# ADC_channel.net
KiCad netlist of a schematic drawn in Altium Designer
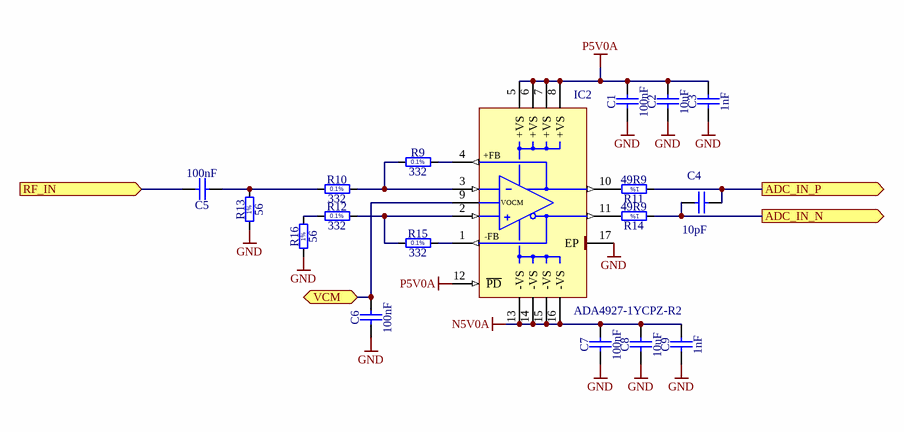
[diagram p0: ADC_channel.SchDoc]

(export (version "E")
  (design (tool "Eeschema 10.0.6"))
  (components
    (comp (ref "C1")
      (value "100nF")
      (footprint "CAPC1005X55N")
      (description "Non-polarised capacitor")
      (fields
        (field (name "PART NUMBER") "CC0402_100NF_16V_10%_X5R")
        (field (name "VOLTAGE") "16V")
        (field (name "AUTHOR") "CERN DEM JLC")
      )
      (libsource (lib "Capacitors") (part "Capacitor - non polarized"))
    )
    (comp (ref "C2")
      (value "10uF")
      (footprint "CAPC1608X87N")
      (description "Non-polarised capacitor")
      (fields
        (field (name "PART NUMBER") "CC0603_10UF_6.3V_20%_X5R")
        (field (name "VOLTAGE") "6.3V")
        (field (name "AUTHOR") "CERN DEM JLC")
      )
      (libsource (lib "Capacitors") (part "Capacitor - non polarized"))
    )
    (comp (ref "C3")
      (value "1nF")
      (footprint "CAPC1005X55N")
      (description "Non-polarised capacitor")
      (fields
        (field (name "PART NUMBER") "CC0402_1NF_50V_10%_X7R")
        (field (name "VOLTAGE") "50V")
        (field (name "AUTHOR") "CERN DEM JLC")
      )
      (libsource (lib "Capacitors") (part "Capacitor - non polarized"))
    )
    (comp (ref "C4")
      (value "10pF")
      (footprint "CAPC1608X87N")
      (description "Non-polarised capacitor")
      (fields
        (field (name "PART NUMBER") "CC0603_10PF_50V_5%_NP0")
        (field (name "VOLTAGE") "50V")
        (field (name "AUTHOR") "CERN DEM JLC")
      )
      (libsource (lib "Capacitors") (part "Capacitor - non polarized"))
    )
    (comp (ref "C5")
      (value "100nF")
      (footprint "CAPC1005X55N")
      (description "Non-polarised capacitor")
      (fields
        (field (name "PART NUMBER") "CC0402_100NF_16V_10%_X5R")
        (field (name "VOLTAGE") "16V")
        (field (name "AUTHOR") "CERN DEM JLC")
      )
      (libsource (lib "Capacitors") (part "Capacitor - non polarized"))
    )
    (comp (ref "C6")
      (value "100nF")
      (footprint "CAPC1005X55N")
      (description "Non-polarised capacitor")
      (fields
        (field (name "PART NUMBER") "CC0402_100NF_16V_10%_X5R")
        (field (name "VOLTAGE") "16V")
        (field (name "AUTHOR") "CERN DEM JLC")
      )
      (libsource (lib "Capacitors") (part "Capacitor - non polarized"))
    )
    (comp (ref "C7")
      (value "100nF")
      (footprint "CAPC1005X55N")
      (description "Non-polarised capacitor")
      (fields
        (field (name "PART NUMBER") "CC0402_100NF_16V_10%_X5R")
        (field (name "VOLTAGE") "16V")
        (field (name "AUTHOR") "CERN DEM JLC")
      )
      (libsource (lib "Capacitors") (part "Capacitor - non polarized"))
    )
    (comp (ref "C8")
      (value "10uF")
      (footprint "CAPC1608X87N")
      (description "Non-polarised capacitor")
      (fields
        (field (name "PART NUMBER") "CC0603_10UF_6.3V_20%_X5R")
        (field (name "VOLTAGE") "6.3V")
        (field (name "AUTHOR") "CERN DEM JLC")
      )
      (libsource (lib "Capacitors") (part "Capacitor - non polarized"))
    )
    (comp (ref "C9")
      (value "1nF")
      (footprint "CAPC1005X55N")
      (description "Non-polarised capacitor")
      (fields
        (field (name "PART NUMBER") "CC0402_1NF_50V_10%_X7R")
        (field (name "VOLTAGE") "50V")
        (field (name "AUTHOR") "CERN DEM JLC")
      )
      (libsource (lib "Capacitors") (part "Capacitor - non polarized"))
    )
    (comp (ref "IC2")
      (value "ADA4927-1YCPZ-R2")
      (footprint "QFN50P300X300X100-17N-S145")
      (description "Ultralow Distortion Current Feedback Differential ADC Driver")
      (fields (field (name "MANUFACTURER") "ANALOG DEVICES") (field (name "AUTHOR") "CERN DEM JLC"))
      (libsource (lib "ICs And Semiconductors") (part "ADA4927-1"))
    )
    (comp (ref "R9")
      (value "332")
      (footprint "RESC1608X55N")
      (description "Resistor - 0.1%")
      (fields
        (field (name "PART NUMBER") "R0603_332R_0.1%_0.063W_10PPM")
        (field (name "POWER") "0.063W")
        (field (name "AUTHOR") "CERN DEM JLC")
      )
      (libsource (lib "Resistors") (part "Resistor - 0.1%"))
    )
    (comp (ref "R10")
      (value "332")
      (footprint "RESC1608X55N")
      (description "Resistor - 0.1%")
      (fields
        (field (name "PART NUMBER") "R0603_332R_0.1%_0.063W_10PPM")
        (field (name "POWER") "0.063W")
        (field (name "AUTHOR") "CERN DEM JLC")
      )
      (libsource (lib "Resistors") (part "Resistor - 0.1%"))
    )
    (comp (ref "R11")
      (value "49R9")
      (footprint "RESC1005X40N")
      (description "Resistor - 1%")
      (fields
        (field (name "PART NUMBER") "R0402_49R9_1%_0.0625W_100PPM")
        (field (name "POWER") "0.0625W")
        (field (name "AUTHOR") "CERN DEM JLC")
      )
      (libsource (lib "Resistors") (part "Resistor - 1%"))
    )
    (comp (ref "R12")
      (value "332")
      (footprint "RESC1608X55N")
      (description "Resistor - 0.1%")
      (fields
        (field (name "PART NUMBER") "R0603_332R_0.1%_0.063W_10PPM")
        (field (name "POWER") "0.063W")
        (field (name "AUTHOR") "CERN DEM JLC")
      )
      (libsource (lib "Resistors") (part "Resistor - 0.1%"))
    )
    (comp (ref "R13")
      (value "56")
      (footprint "RESC1005X40N")
      (description "Resistor - 1%")
      (fields
        (field (name "PART NUMBER") "R0402_56R_1%_0.0625W_100PPM")
        (field (name "POWER") "0.0625W")
        (field (name "AUTHOR") "CERN DEM JLC")
      )
      (libsource (lib "Resistors") (part "Resistor - 1%"))
    )
    (comp (ref "R14")
      (value "49R9")
      (footprint "RESC1005X40N")
      (description "Resistor - 1%")
      (fields
        (field (name "PART NUMBER") "R0402_49R9_1%_0.0625W_100PPM")
        (field (name "POWER") "0.0625W")
        (field (name "AUTHOR") "CERN DEM JLC")
      )
      (libsource (lib "Resistors") (part "Resistor - 1%"))
    )
    (comp (ref "R15")
      (value "332")
      (footprint "RESC1608X55N")
      (description "Resistor - 0.1%")
      (fields
        (field (name "PART NUMBER") "R0603_332R_0.1%_0.063W_10PPM")
        (field (name "POWER") "0.063W")
        (field (name "AUTHOR") "CERN DEM JLC")
      )
      (libsource (lib "Resistors") (part "Resistor - 0.1%"))
    )
    (comp (ref "R16")
      (value "56")
      (footprint "RESC1005X40N")
      (description "Resistor - 1%")
      (fields
        (field (name "PART NUMBER") "R0402_56R_1%_0.0625W_100PPM")
        (field (name "POWER") "0.0625W")
        (field (name "AUTHOR") "CERN DEM JLC")
      )
      (libsource (lib "Resistors") (part "Resistor - 1%"))
    )
  )
  (nets
    (net (code "1") (name "/ADC_IN_N") (class "Default")
      (node (ref "C4") (pin "1") (pinfunction "1_1") (pintype "passive"))
      (node (ref "R14") (pin "1") (pinfunction "1_1") (pintype "passive"))
    )
    (net (code "2") (name "/ADC_IN_P") (class "Default")
      (node (ref "C4") (pin "2") (pinfunction "2_2") (pintype "passive"))
      (node (ref "R11") (pin "1") (pinfunction "1_1") (pintype "passive"))
    )
    (net (code "3") (name "/RF_IN") (class "Default")
      (node (ref "C5") (pin "2") (pinfunction "2_2") (pintype "passive"))
    )
    (net (code "4") (name "/VCM") (class "Default")
      (node (ref "C6") (pin "2") (pinfunction "2_2") (pintype "passive"))
      (node (ref "IC2") (pin "9") (pinfunction "VOCM_9") (pintype "passive"))
    )
    (net (code "5") (name "GND") (class "Default")
      (node (ref "C1") (pin "1") (pinfunction "1_1") (pintype "passive"))
      (node (ref "C2") (pin "1") (pinfunction "1_1") (pintype "passive"))
      (node (ref "C3") (pin "1") (pinfunction "1_1") (pintype "passive"))
      (node (ref "C6") (pin "1") (pinfunction "1_1") (pintype "passive"))
      (node (ref "C7") (pin "1") (pinfunction "1_1") (pintype "passive"))
      (node (ref "C8") (pin "1") (pinfunction "1_1") (pintype "passive"))
      (node (ref "C9") (pin "1") (pinfunction "1_1") (pintype "passive"))
      (node (ref "IC2") (pin "17") (pinfunction "EP_17") (pintype "power_in"))
      (node (ref "R13") (pin "1") (pinfunction "1_1") (pintype "passive"))
      (node (ref "R16") (pin "1") (pinfunction "1_1") (pintype "passive"))
    )
    (net (code "6") (name "N5V0A") (class "Default")
      (node (ref "C7") (pin "2") (pinfunction "2_2") (pintype "passive"))
      (node (ref "C8") (pin "2") (pinfunction "2_2") (pintype "passive"))
      (node (ref "C9") (pin "2") (pinfunction "2_2") (pintype "passive"))
      (node (ref "IC2") (pin "13") (pinfunction "-VS_13") (pintype "power_in"))
      (node (ref "IC2") (pin "14") (pinfunction "-VS_14") (pintype "power_in"))
      (node (ref "IC2") (pin "15") (pinfunction "-VS_15") (pintype "power_in"))
      (node (ref "IC2") (pin "16") (pinfunction "-VS_16") (pintype "power_in"))
    )
    (net (code "7") (name "Net-(C5-Pad1)") (class "Default")
      (node (ref "C5") (pin "1") (pinfunction "1_1") (pintype "passive"))
      (node (ref "R10") (pin "1") (pinfunction "1_1") (pintype "passive"))
      (node (ref "R13") (pin "2") (pinfunction "2_2") (pintype "passive"))
    )
    (net (code "8") (name "Net-(IC2-+FB)") (class "Default")
      (node (ref "IC2") (pin "4") (pinfunction "+FB_4") (pintype "output"))
      (node (ref "R9") (pin "2") (pinfunction "2_2") (pintype "passive"))
    )
    (net (code "9") (name "Net-(IC2-+IN)") (class "Default")
      (node (ref "IC2") (pin "2") (pinfunction "+IN_2") (pintype "input"))
      (node (ref "R12") (pin "2") (pinfunction "2_2") (pintype "passive"))
      (node (ref "R15") (pin "1") (pinfunction "1_1") (pintype "passive"))
    )
    (net (code "10") (name "Net-(IC2-+OUT)") (class "Default")
      (node (ref "IC2") (pin "10") (pinfunction "+OUT_10") (pintype "output"))
      (node (ref "R11") (pin "2") (pinfunction "2_2") (pintype "passive"))
    )
    (net (code "11") (name "Net-(IC2--FB)") (class "Default")
      (node (ref "IC2") (pin "1") (pinfunction "-FB_1") (pintype "output"))
      (node (ref "R15") (pin "2") (pinfunction "2_2") (pintype "passive"))
    )
    (net (code "12") (name "Net-(IC2--IN)") (class "Default")
      (node (ref "IC2") (pin "3") (pinfunction "-IN_3") (pintype "input"))
      (node (ref "R10") (pin "2") (pinfunction "2_2") (pintype "passive"))
      (node (ref "R9") (pin "1") (pinfunction "1_1") (pintype "passive"))
    )
    (net (code "13") (name "Net-(IC2--OUT)") (class "Default")
      (node (ref "IC2") (pin "11") (pinfunction "-OUT_11") (pintype "output"))
      (node (ref "R14") (pin "2") (pinfunction "2_2") (pintype "passive"))
    )
    (net (code "14") (name "Net-(R12-Pad1)") (class "Default")
      (node (ref "R12") (pin "1") (pinfunction "1_1") (pintype "passive"))
      (node (ref "R16") (pin "2") (pinfunction "2_2") (pintype "passive"))
    )
    (net (code "15") (name "P5V0A") (class "Default")
      (node (ref "C1") (pin "2") (pinfunction "2_2") (pintype "passive"))
      (node (ref "C2") (pin "2") (pinfunction "2_2") (pintype "passive"))
      (node (ref "C3") (pin "2") (pinfunction "2_2") (pintype "passive"))
      (node (ref "IC2") (pin "12") (pinfunction "~{PD}_12") (pintype "input"))
      (node (ref "IC2") (pin "5") (pinfunction "+VS_5") (pintype "power_in"))
      (node (ref "IC2") (pin "6") (pinfunction "+VS_6") (pintype "power_in"))
      (node (ref "IC2") (pin "7") (pinfunction "+VS_7") (pintype "power_in"))
      (node (ref "IC2") (pin "8") (pinfunction "+VS_8") (pintype "power_in"))
    )
  )
)
